# HAMINTORI.net
KiCad netlist of a schematic drawn in Altium Designer
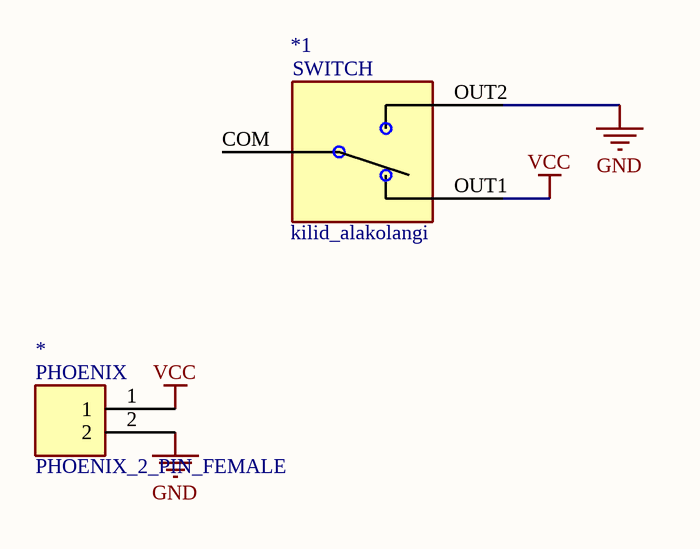
[diagram p0: HAMINTORI.SchDoc]

(export (version "E")
  (design (tool "Eeschema 10.0.6"))
  (components
    (comp (ref "*")
      (value "PHOENIX_2_PIN_FEMALE")
      (footprint "PHOENIX_2_PIN_FEMALE")
      (libsource (lib "PHOENIX_2_PIN_FEMALE") (part "PHOENIX_2_PIN_FEMALE"))
    )
    (comp (ref "*1")
      (value "kilid_alakolangi")
      (footprint "kilid_alakolangi")
      (libsource (lib "kilid_alakolangi") (part "kilid_alakolangi"))
    )
  )
  (nets
    (net (code "1") (name "GND") (class "Default")
      (node (ref "*") (pin "2") (pinfunction "2_2") (pintype "passive"))
      (node (ref "*1") (pin "OUT2") (pinfunction "OUT2_OUT2") (pintype "passive"))
    )
    (net (code "2") (name "VCC") (class "Default")
      (node (ref "*") (pin "1") (pinfunction "1_1") (pintype "passive"))
      (node (ref "*1") (pin "OUT1") (pinfunction "OUT1_OUT1") (pintype "passive"))
    )
    (net (code "3") (name "unconnected-(*1-PadCOM)") (class "Default")
      (node (ref "*1") (pin "COM") (pinfunction "COM_COM") (pintype "passive"))
    )
  )
)
